# Mabee_Slide_Potentimeter_V1_1.net
KiCad netlist of a schematic drawn in EAGLE
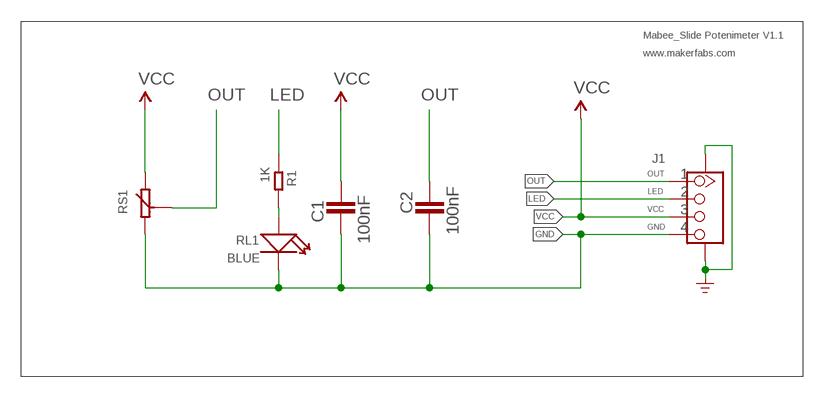
[diagram p0: schematic, sheet 1]

(export (version "E")
  (design (tool "Eeschema 10.0.6"))
  (components
    (comp (ref "C1")
      (value "100nF")
      (footprint "eagle-import:C0603")
      (libsource (lib "eagle-import") (part "C-EUC0603"))
    )
    (comp (ref "C2")
      (value "100nF")
      (footprint "eagle-import:C0603")
      (libsource (lib "eagle-import") (part "C-EUC0603"))
    )
    (comp (ref "J1")
      (value "GROVE-CONNECTOR-SMD'90D'")
      (footprint "eagle-import:HW4-SMD-2.0-90D")
      (libsource (lib "eagle-import") (part "GROVE-CONNECTOR-SMD'90D'"))
    )
    (comp (ref "R1")
      (value "1K")
      (footprint "eagle-import:R0603")
      (libsource (lib "eagle-import") (part "R-0603"))
    )
    (comp (ref "RL1")
      (value "BLUE")
      (footprint "eagle-import:LED-0603")
      (libsource (lib "eagle-import") (part "LED'0603'"))
    )
    (comp (ref "RS1")
      (value "R_SLIDE")
      (footprint "eagle-import:R_SLIDE_DPT")
      (libsource (lib "eagle-import") (part "R_SLIDE"))
    )
  )
  (nets
    (net (code "1") (name "GND") (class "Default")
      (node (ref "C1") (pin "1") (pinfunction "1_1") (pintype "passive"))
      (node (ref "C2") (pin "1") (pinfunction "1_1") (pintype "passive"))
      (node (ref "J1") (pin "4") (pinfunction "4_4") (pintype "bidirectional"))
      (node (ref "J1") (pin "SS1") (pinfunction "SS1_SS1") (pintype "bidirectional"))
      (node (ref "J1") (pin "SS2") (pinfunction "SS2_SS2") (pintype "bidirectional"))
      (node (ref "RL1") (pin "-") (pinfunction "-_-") (pintype "passive"))
      (node (ref "RS1") (pin "3") (pinfunction "3_3") (pintype "bidirectional"))
    )
    (net (code "2") (name "LED") (class "Default")
      (node (ref "J1") (pin "2") (pinfunction "2_2") (pintype "bidirectional"))
      (node (ref "R1") (pin "1") (pinfunction "1_1") (pintype "passive"))
    )
    (net (code "3") (name "Net-(R1-Pad2)") (class "Default")
      (node (ref "R1") (pin "2") (pinfunction "2_2") (pintype "passive"))
      (node (ref "RL1") (pin "+") (pinfunction "+_+") (pintype "passive"))
    )
    (net (code "4") (name "OUT") (class "Default")
      (node (ref "C2") (pin "2") (pinfunction "2_2") (pintype "passive"))
      (node (ref "J1") (pin "1") (pinfunction "1_1") (pintype "bidirectional"))
      (node (ref "RS1") (pin "2") (pinfunction "2_2") (pintype "bidirectional"))
    )
    (net (code "5") (name "VCC") (class "Default")
      (node (ref "C1") (pin "2") (pinfunction "2_2") (pintype "passive"))
      (node (ref "J1") (pin "3") (pinfunction "3_3") (pintype "bidirectional"))
      (node (ref "RS1") (pin "1") (pinfunction "1_1") (pintype "bidirectional"))
    )
  )
)
